# Connector.net
KiCad netlist of a schematic drawn in Altium Designer
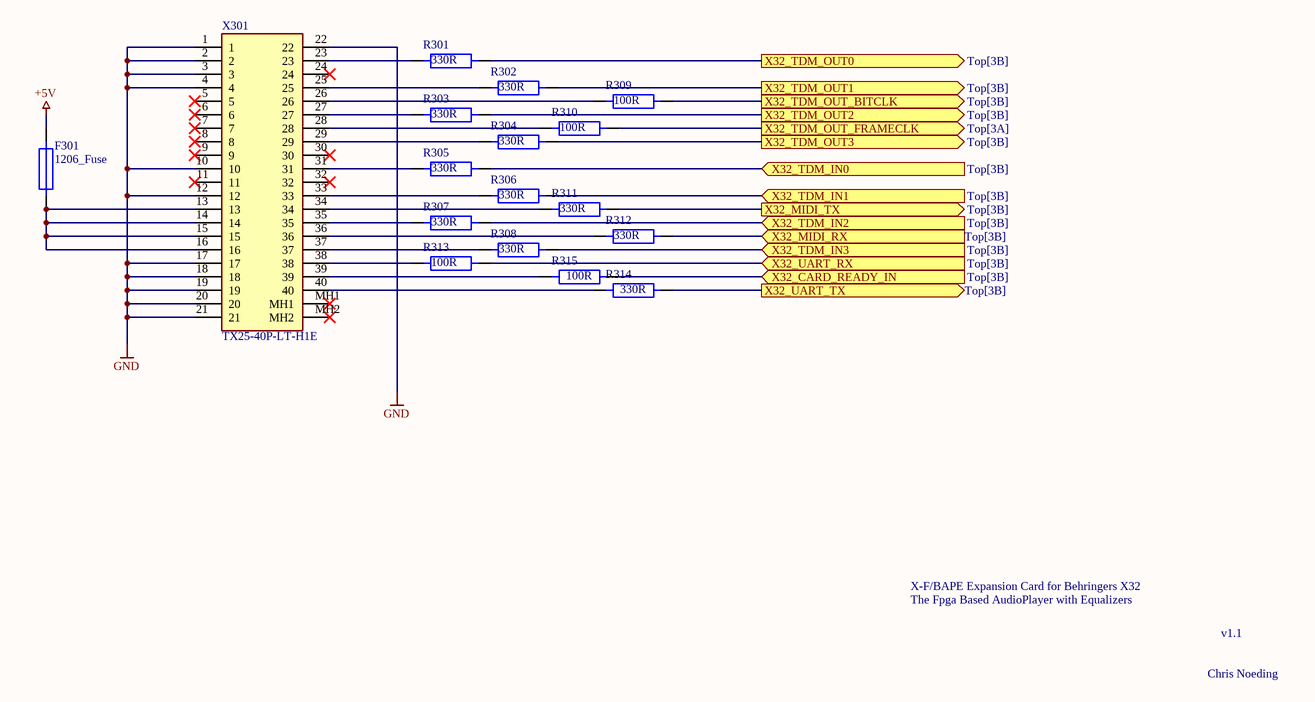
[diagram p0: Connector.SchDoc]

(export (version "E")
  (design (tool "Eeschema 10.0.6"))
  (components
    (comp (ref "F301")
      (value "1206_Fuse")
      (footprint "1206")
      (libsource (lib "FPGA_Board_Library") (part "1206_Fuse"))
    )
    (comp (ref "R301")
      (value "330R")
      (footprint "1206")
      (description "1206_R")
      (libsource (lib "FPGA_Board_Library") (part "1206_R"))
    )
    (comp (ref "R302")
      (value "330R")
      (footprint "1206")
      (description "1206_R")
      (libsource (lib "FPGA_Board_Library") (part "1206_R"))
    )
    (comp (ref "R303")
      (value "330R")
      (footprint "1206")
      (description "1206_R")
      (libsource (lib "FPGA_Board_Library") (part "1206_R"))
    )
    (comp (ref "R304")
      (value "330R")
      (footprint "1206")
      (description "1206_R")
      (libsource (lib "FPGA_Board_Library") (part "1206_R"))
    )
    (comp (ref "R305")
      (value "330R")
      (footprint "1206")
      (libsource (lib "FPGA_Board_Library") (part "1206_R"))
    )
    (comp (ref "R306")
      (value "330R")
      (footprint "1206")
      (libsource (lib "FPGA_Board_Library") (part "1206_R"))
    )
    (comp (ref "R307")
      (value "330R")
      (footprint "1206")
      (description "1206_R")
      (libsource (lib "FPGA_Board_Library") (part "1206_R"))
    )
    (comp (ref "R308")
      (value "330R")
      (footprint "1206")
      (description "1206_R")
      (libsource (lib "FPGA_Board_Library") (part "1206_R"))
    )
    (comp (ref "R309")
      (value "100R")
      (footprint "1206")
      (description "1206_R")
      (libsource (lib "FPGA_Board_Library") (part "1206_R"))
    )
    (comp (ref "R310")
      (value "100R")
      (footprint "1206")
      (description "1206_R")
      (libsource (lib "FPGA_Board_Library") (part "1206_R"))
    )
    (comp (ref "R311")
      (value "330R")
      (footprint "1206")
      (description "1206_R")
      (libsource (lib "FPGA_Board_Library") (part "1206_R"))
    )
    (comp (ref "R312")
      (value "330R")
      (footprint "1206")
      (description "1206_R")
      (libsource (lib "FPGA_Board_Library") (part "1206_R"))
    )
    (comp (ref "R313")
      (value "100R")
      (footprint "1206")
      (description "1206_R")
      (libsource (lib "FPGA_Board_Library") (part "1206_R"))
    )
    (comp (ref "R314")
      (value "330R")
      (footprint "1206")
      (description "1206_R")
      (libsource (lib "FPGA_Board_Library") (part "1206_R"))
    )
    (comp (ref "R315")
      (value "100R")
      (footprint "1206")
      (description "1206_R")
      (libsource (lib "FPGA_Board_Library") (part "1206_R"))
    )
    (comp (ref "X301")
      (value "TX25-40P-LT-H1E")
      (footprint "SamacSys:TX2540PLTH1E")
      (description "Connector")
      (fields (field (name "MOUSER PART NUMBER") "656-TX25-40P-LT-H1E"))
      (libsource (lib "SamacSys") (part "TX25-40P-LT-H1E"))
    )
  )
  (nets
    (net (code "1") (name "+5V") (class "Default")
      (node (ref "F301") (pin "2") (pinfunction "2_2") (pintype "passive"))
    )
    (net (code "2") (name "/X32_CARD_READY_IN") (class "Default")
      (node (ref "R315") (pin "2") (pinfunction "2_2") (pintype "passive"))
    )
    (net (code "3") (name "/X32_MIDI_RX") (class "Default")
      (node (ref "R312") (pin "2") (pinfunction "2_2") (pintype "passive"))
    )
    (net (code "4") (name "/X32_MIDI_TX") (class "Default")
      (node (ref "R311") (pin "2") (pinfunction "2_2") (pintype "passive"))
    )
    (net (code "5") (name "/X32_TDM_IN0") (class "Default")
      (node (ref "R305") (pin "2") (pinfunction "2_2") (pintype "passive"))
    )
    (net (code "6") (name "/X32_TDM_IN1") (class "Default")
      (node (ref "R306") (pin "2") (pinfunction "2_2") (pintype "passive"))
    )
    (net (code "7") (name "/X32_TDM_IN2") (class "Default")
      (node (ref "R307") (pin "2") (pinfunction "2_2") (pintype "passive"))
    )
    (net (code "8") (name "/X32_TDM_IN3") (class "Default")
      (node (ref "R308") (pin "2") (pinfunction "2_2") (pintype "passive"))
    )
    (net (code "9") (name "/X32_TDM_OUT0") (class "Default")
      (node (ref "R301") (pin "2") (pinfunction "2_2") (pintype "passive"))
    )
    (net (code "10") (name "/X32_TDM_OUT1") (class "Default")
      (node (ref "R302") (pin "2") (pinfunction "2_2") (pintype "passive"))
    )
    (net (code "11") (name "/X32_TDM_OUT2") (class "Default")
      (node (ref "R303") (pin "2") (pinfunction "2_2") (pintype "passive"))
    )
    (net (code "12") (name "/X32_TDM_OUT3") (class "Default")
      (node (ref "R304") (pin "2") (pinfunction "2_2") (pintype "passive"))
    )
    (net (code "13") (name "/X32_TDM_OUT_BITCLK") (class "Default")
      (node (ref "R309") (pin "2") (pinfunction "2_2") (pintype "passive"))
    )
    (net (code "14") (name "/X32_TDM_OUT_FRAMECLK") (class "Default")
      (node (ref "R310") (pin "2") (pinfunction "2_2") (pintype "passive"))
    )
    (net (code "15") (name "/X32_UART_RX") (class "Default")
      (node (ref "R313") (pin "2") (pinfunction "2_2") (pintype "passive"))
    )
    (net (code "16") (name "/X32_UART_TX") (class "Default")
      (node (ref "R314") (pin "2") (pinfunction "2_2") (pintype "passive"))
    )
    (net (code "17") (name "GND") (class "Default")
      (node (ref "X301") (pin "1") (pinfunction "1_1") (pintype "passive"))
      (node (ref "X301") (pin "10") (pinfunction "10_10") (pintype "passive"))
      (node (ref "X301") (pin "12") (pinfunction "12_12") (pintype "passive"))
      (node (ref "X301") (pin "17") (pinfunction "17_17") (pintype "passive"))
      (node (ref "X301") (pin "18") (pinfunction "18_18") (pintype "passive"))
      (node (ref "X301") (pin "19") (pinfunction "19_19") (pintype "passive"))
      (node (ref "X301") (pin "2") (pinfunction "2_2") (pintype "passive"))
      (node (ref "X301") (pin "20") (pinfunction "20_20") (pintype "passive"))
      (node (ref "X301") (pin "21") (pinfunction "21_21") (pintype "passive"))
      (node (ref "X301") (pin "22") (pinfunction "22_22") (pintype "passive"))
      (node (ref "X301") (pin "3") (pinfunction "3_3") (pintype "passive"))
      (node (ref "X301") (pin "4") (pinfunction "4_4") (pintype "passive"))
    )
    (net (code "18") (name "Net-(F301-Pad1)") (class "Default")
      (node (ref "F301") (pin "1") (pinfunction "1_1") (pintype "passive"))
      (node (ref "X301") (pin "13") (pinfunction "13_13") (pintype "passive"))
      (node (ref "X301") (pin "14") (pinfunction "14_14") (pintype "passive"))
      (node (ref "X301") (pin "15") (pinfunction "15_15") (pintype "passive"))
      (node (ref "X301") (pin "16") (pinfunction "16_16") (pintype "passive"))
    )
    (net (code "19") (name "Net-(R301-Pad1)") (class "Default")
      (node (ref "R301") (pin "1") (pinfunction "1_1") (pintype "passive"))
      (node (ref "X301") (pin "23") (pinfunction "23_23") (pintype "passive"))
    )
    (net (code "20") (name "Net-(R302-Pad1)") (class "Default")
      (node (ref "R302") (pin "1") (pinfunction "1_1") (pintype "passive"))
      (node (ref "X301") (pin "25") (pinfunction "25_25") (pintype "passive"))
    )
    (net (code "21") (name "Net-(R303-Pad1)") (class "Default")
      (node (ref "R303") (pin "1") (pinfunction "1_1") (pintype "passive"))
      (node (ref "X301") (pin "27") (pinfunction "27_27") (pintype "passive"))
    )
    (net (code "22") (name "Net-(R304-Pad1)") (class "Default")
      (node (ref "R304") (pin "1") (pinfunction "1_1") (pintype "passive"))
      (node (ref "X301") (pin "29") (pinfunction "29_29") (pintype "passive"))
    )
    (net (code "23") (name "Net-(R305-Pad1)") (class "Default")
      (node (ref "R305") (pin "1") (pinfunction "1_1") (pintype "passive"))
      (node (ref "X301") (pin "31") (pinfunction "31_31") (pintype "passive"))
    )
    (net (code "24") (name "Net-(R306-Pad1)") (class "Default")
      (node (ref "R306") (pin "1") (pinfunction "1_1") (pintype "passive"))
      (node (ref "X301") (pin "33") (pinfunction "33_33") (pintype "passive"))
    )
    (net (code "25") (name "Net-(R307-Pad1)") (class "Default")
      (node (ref "R307") (pin "1") (pinfunction "1_1") (pintype "passive"))
      (node (ref "X301") (pin "35") (pinfunction "35_35") (pintype "passive"))
    )
    (net (code "26") (name "Net-(R308-Pad1)") (class "Default")
      (node (ref "R308") (pin "1") (pinfunction "1_1") (pintype "passive"))
      (node (ref "X301") (pin "37") (pinfunction "37_37") (pintype "passive"))
    )
    (net (code "27") (name "Net-(R309-Pad1)") (class "Default")
      (node (ref "R309") (pin "1") (pinfunction "1_1") (pintype "passive"))
      (node (ref "X301") (pin "26") (pinfunction "26_26") (pintype "passive"))
    )
    (net (code "28") (name "Net-(R310-Pad1)") (class "Default")
      (node (ref "R310") (pin "1") (pinfunction "1_1") (pintype "passive"))
      (node (ref "X301") (pin "28") (pinfunction "28_28") (pintype "passive"))
    )
    (net (code "29") (name "Net-(R311-Pad1)") (class "Default")
      (node (ref "R311") (pin "1") (pinfunction "1_1") (pintype "passive"))
      (node (ref "X301") (pin "34") (pinfunction "34_34") (pintype "passive"))
    )
    (net (code "30") (name "Net-(R312-Pad1)") (class "Default")
      (node (ref "R312") (pin "1") (pinfunction "1_1") (pintype "passive"))
      (node (ref "X301") (pin "36") (pinfunction "36_36") (pintype "passive"))
    )
    (net (code "31") (name "Net-(R313-Pad1)") (class "Default")
      (node (ref "R313") (pin "1") (pinfunction "1_1") (pintype "passive"))
      (node (ref "X301") (pin "38") (pinfunction "38_38") (pintype "passive"))
    )
    (net (code "32") (name "Net-(R314-Pad1)") (class "Default")
      (node (ref "R314") (pin "1") (pinfunction "1_1") (pintype "passive"))
      (node (ref "X301") (pin "40") (pinfunction "40_40") (pintype "passive"))
    )
    (net (code "33") (name "Net-(R315-Pad1)") (class "Default")
      (node (ref "R315") (pin "1") (pinfunction "1_1") (pintype "passive"))
      (node (ref "X301") (pin "39") (pinfunction "39_39") (pintype "passive"))
    )
    (net (code "34") (name "unconnected-(X301-Pad5)") (class "Default")
      (node (ref "X301") (pin "5") (pinfunction "5_5") (pintype "passive+no_connect"))
    )
    (net (code "35") (name "unconnected-(X301-Pad6)") (class "Default")
      (node (ref "X301") (pin "6") (pinfunction "6_6") (pintype "passive+no_connect"))
    )
    (net (code "36") (name "unconnected-(X301-Pad7)") (class "Default")
      (node (ref "X301") (pin "7") (pinfunction "7_7") (pintype "passive+no_connect"))
    )
    (net (code "37") (name "unconnected-(X301-Pad8)") (class "Default")
      (node (ref "X301") (pin "8") (pinfunction "8_8") (pintype "passive+no_connect"))
    )
    (net (code "38") (name "unconnected-(X301-Pad9)") (class "Default")
      (node (ref "X301") (pin "9") (pinfunction "9_9") (pintype "passive+no_connect"))
    )
    (net (code "39") (name "unconnected-(X301-Pad11)") (class "Default")
      (node (ref "X301") (pin "11") (pinfunction "11_11") (pintype "passive+no_connect"))
    )
    (net (code "40") (name "unconnected-(X301-Pad24)") (class "Default")
      (node (ref "X301") (pin "24") (pinfunction "24_24") (pintype "passive+no_connect"))
    )
    (net (code "41") (name "unconnected-(X301-Pad30)") (class "Default")
      (node (ref "X301") (pin "30") (pinfunction "30_30") (pintype "passive+no_connect"))
    )
    (net (code "42") (name "unconnected-(X301-Pad32)") (class "Default")
      (node (ref "X301") (pin "32") (pinfunction "32_32") (pintype "passive+no_connect"))
    )
    (net (code "43") (name "unconnected-(X301-PadMH1)") (class "Default")
      (node (ref "X301") (pin "MH1") (pinfunction "MH1_MH1") (pintype "passive+no_connect"))
    )
    (net (code "44") (name "unconnected-(X301-PadMH2)") (class "Default")
      (node (ref "X301") (pin "MH2") (pinfunction "MH2_MH2") (pintype "passive+no_connect"))
    )
  )
)
